# sensors_actuators_shieldv2_1.net
KiCad netlist of a schematic drawn in EAGLE
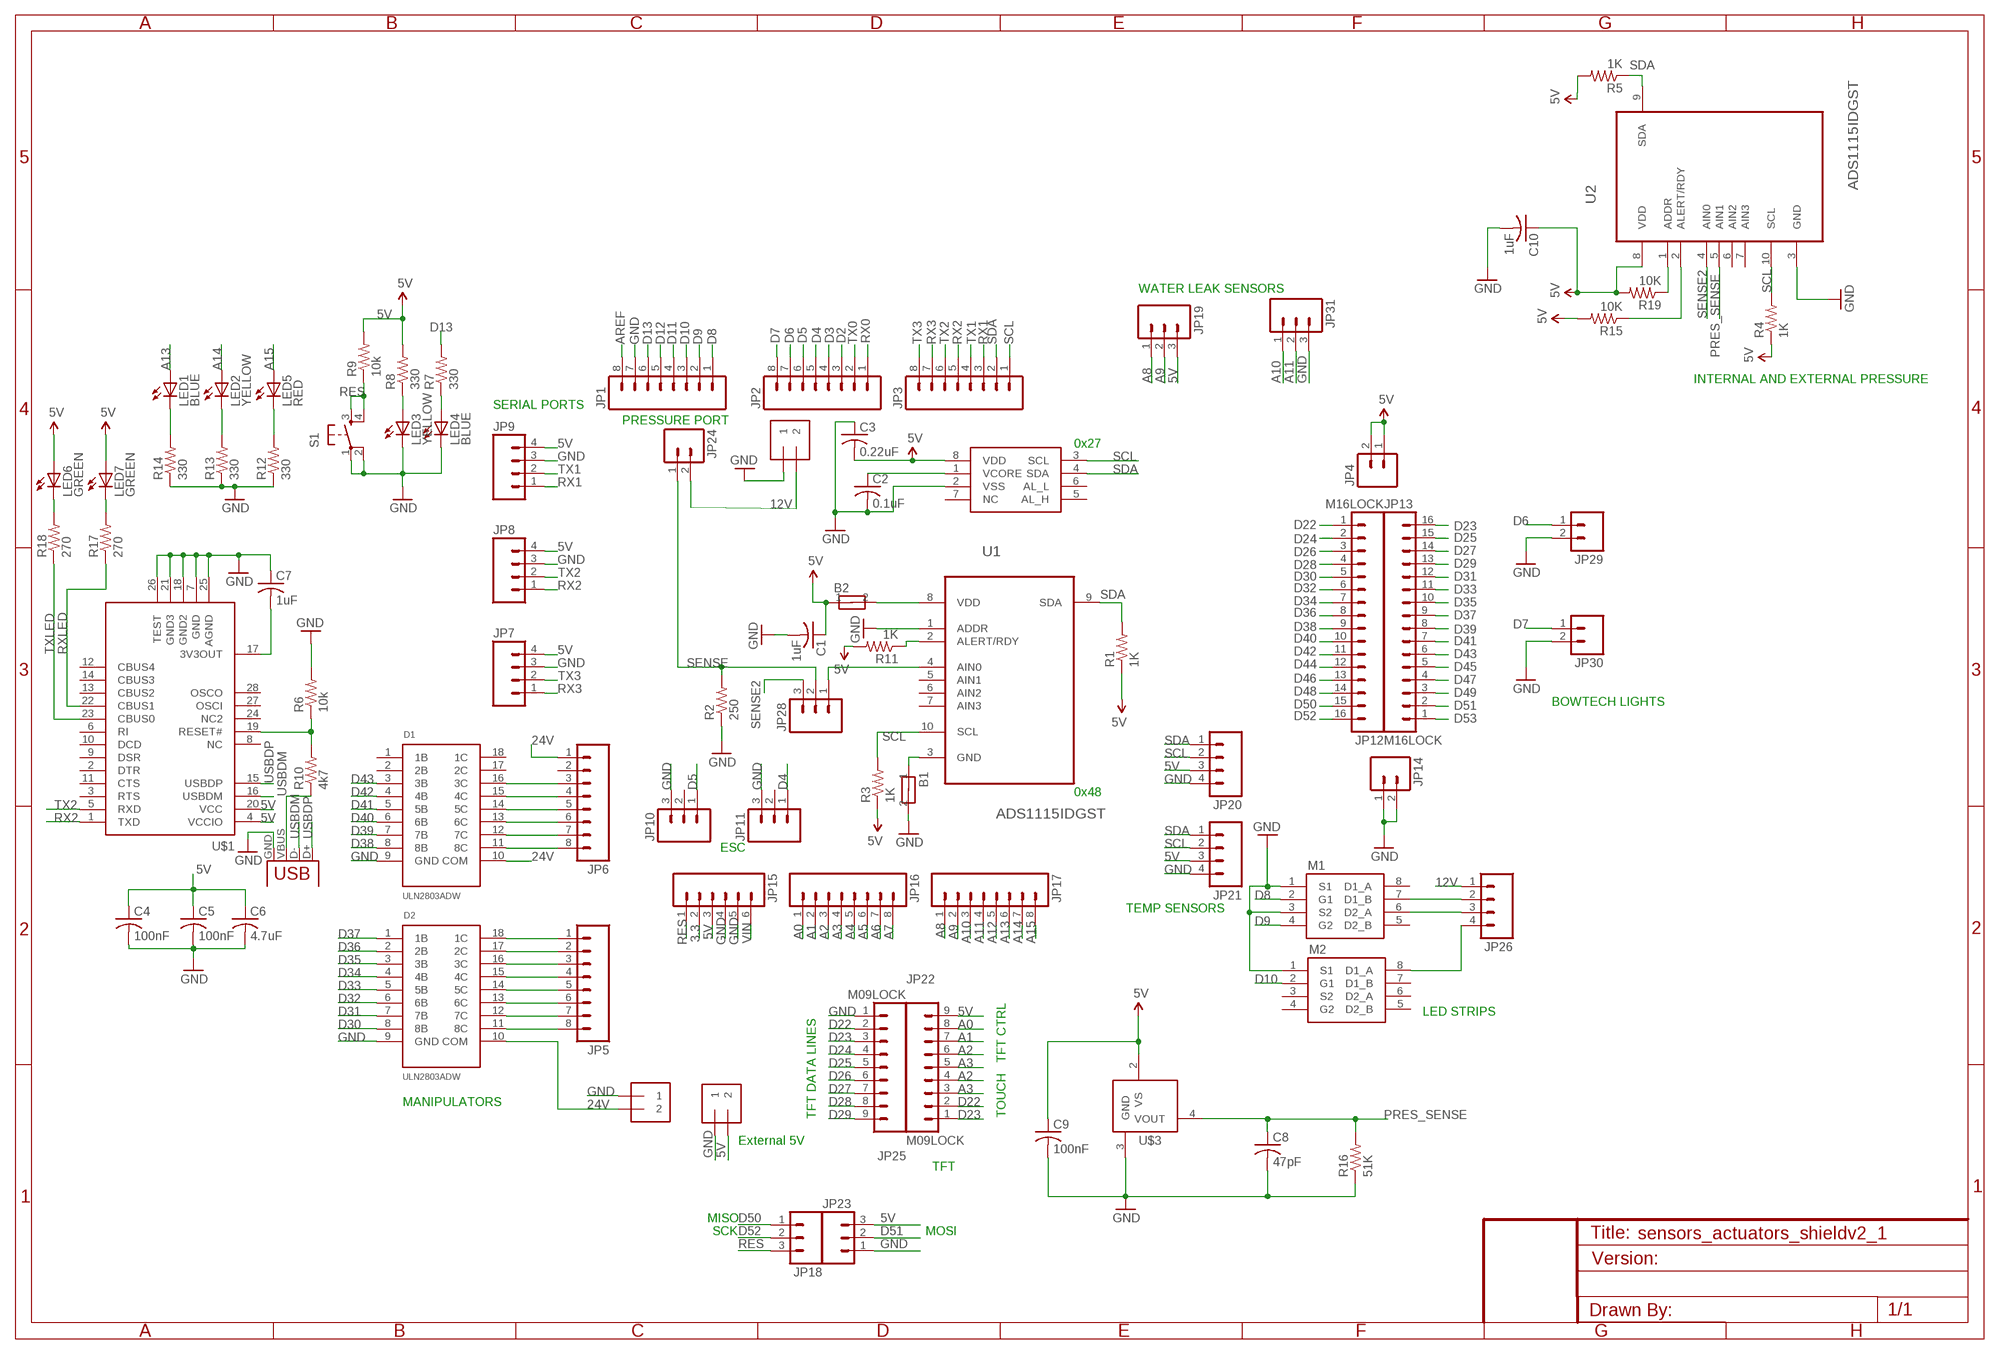
[diagram p0: schematic, sheet 1]

(export (version "E")
  (design (tool "Eeschema 10.0.6"))
  (components
    (comp (ref "B1")
      (value "MMZ2012Y152B0.4OHM,500MA")
      (footprint "eagle-import:0805")
      (fields (field (name "MPN") "MMZ2012Y152B"))
      (libsource (lib "eagle-import") (part "MMZ2012Y152B0.4OHM,500MA"))
    )
    (comp (ref "B2")
      (value "MMZ2012Y152B0.4OHM,500MA")
      (footprint "eagle-import:0805")
      (fields (field (name "MPN") "MMZ2012Y152B"))
      (libsource (lib "eagle-import") (part "MMZ2012Y152B0.4OHM,500MA"))
    )
    (comp (ref "C1")
      (value "1uF")
      (footprint "eagle-import:C0805")
      (fields (field (name "MF") "KEMET") (field (name "MPN") "C0805C105M4RACTU"))
      (libsource (lib "eagle-import") (part "C-USC0805"))
    )
    (comp (ref "C2")
      (value "0.1uF")
      (footprint "eagle-import:C0805")
      (fields (field (name "MPN") "08055C104K4Z2A"))
      (libsource (lib "eagle-import") (part "C-USC0805"))
    )
    (comp (ref "C3")
      (value "0.22uF")
      (footprint "eagle-import:C0805")
      (fields (field (name "MPN") "CGA4J2X8R1E224K125AA"))
      (libsource (lib "eagle-import") (part "C-USC0805"))
    )
    (comp (ref "C4")
      (value "100nF")
      (footprint "eagle-import:C0805")
      (fields (field (name "MPN") "MC0805B104J500CT"))
      (libsource (lib "eagle-import") (part "C-USC0805"))
    )
    (comp (ref "C5")
      (value "100nF")
      (footprint "eagle-import:C0805")
      (fields (field (name "MPN") "MC0805B104J500CT"))
      (libsource (lib "eagle-import") (part "C-USC0805"))
    )
    (comp (ref "C6")
      (value "4.7uF")
      (footprint "eagle-import:C0805")
      (fields (field (name "MPN") "C2012X5R1A475K125AA"))
      (libsource (lib "eagle-import") (part "C-USC0805"))
    )
    (comp (ref "C7")
      (value "1uF")
      (footprint "eagle-import:C0805")
      (fields (field (name "MF") "KEMET") (field (name "MPN") "C0805C105M4RACTU"))
      (libsource (lib "eagle-import") (part "C-USC0805"))
    )
    (comp (ref "C8")
      (value "47pF")
      (footprint "eagle-import:C0805")
      (fields (field (name "MF") "VISHAY/VITRAMON") (field (name "MPN") "VJ0805A470KXAMT"))
      (libsource (lib "eagle-import") (part "C-USC0805"))
    )
    (comp (ref "C9")
      (value "100nF")
      (footprint "eagle-import:C0805")
      (fields (field (name "MPN") "MC0805B104J500CT"))
      (libsource (lib "eagle-import") (part "C-USC0805"))
    )
    (comp (ref "C10")
      (value "1uF")
      (footprint "eagle-import:C0805")
      (fields (field (name "MF") "KEMET") (field (name "MPN") "C0805C105M4RACTU"))
      (libsource (lib "eagle-import") (part "C-USC0805"))
    )
    (comp (ref "D1")
      (value "ULN2803ADW")
      (footprint "eagle-import:SOIC")
      (fields (field (name "MF") "TEXAS INSTRUMENTS"))
      (libsource (lib "eagle-import") (part "ULN2803ADW"))
    )
    (comp (ref "D2")
      (value "ULN2803ADW")
      (footprint "eagle-import:SOIC")
      (fields (field (name "MF") "TEXAS INSTRUMENTS"))
      (libsource (lib "eagle-import") (part "ULN2803ADW"))
    )
    (comp (ref "J1")
      (value "1X2-3.5MM")
      (footprint "eagle-import:1X2-3.5MM")
      (fields (field (name "MPN") "691103110002"))
      (libsource (lib "eagle-import") (part "1X2-3.5MM"))
    )
    (comp (ref "J2")
      (value "1X2-3.5MM")
      (footprint "eagle-import:1X2-3.5MM")
      (fields (field (name "MPN") "691103110002"))
      (libsource (lib "eagle-import") (part "1X2-3.5MM"))
    )
    (comp (ref "J3")
      (value "1X2-3.5MM")
      (footprint "eagle-import:1X2-3.5MM")
      (fields (field (name "MPN") "691103110002"))
      (libsource (lib "eagle-import") (part "1X2-3.5MM"))
    )
    (comp (ref "JP1")
      (value "M08LOCK")
      (footprint "eagle-import:1X08_LOCK")
      (libsource (lib "eagle-import") (part "M08LOCK"))
    )
    (comp (ref "JP2")
      (value "M08LOCK")
      (footprint "eagle-import:1X08_LOCK")
      (libsource (lib "eagle-import") (part "M08LOCK"))
    )
    (comp (ref "JP3")
      (value "M08LOCK")
      (footprint "eagle-import:1X08_LOCK")
      (libsource (lib "eagle-import") (part "M08LOCK"))
    )
    (comp (ref "JP4")
      (value "M02LOCK")
      (footprint "eagle-import:1X02_LOCK")
      (libsource (lib "eagle-import") (part "M02LOCK"))
    )
    (comp (ref "JP5")
      (value "M08LOCK")
      (footprint "eagle-import:1X08_LOCK")
      (libsource (lib "eagle-import") (part "M08LOCK"))
    )
    (comp (ref "JP6")
      (value "M08LOCK")
      (footprint "eagle-import:1X08_LOCK")
      (libsource (lib "eagle-import") (part "M08LOCK"))
    )
    (comp (ref "JP7")
      (value "M04LOCK")
      (footprint "eagle-import:1X04_LOCK")
      (libsource (lib "eagle-import") (part "M04LOCK"))
    )
    (comp (ref "JP8")
      (value "M04LOCK")
      (footprint "eagle-import:1X04_LOCK")
      (libsource (lib "eagle-import") (part "M04LOCK"))
    )
    (comp (ref "JP9")
      (value "M04LOCK")
      (footprint "eagle-import:1X04_LOCK")
      (libsource (lib "eagle-import") (part "M04LOCK"))
    )
    (comp (ref "JP10")
      (value "M03LOCK")
      (footprint "eagle-import:1X03_LOCK")
      (libsource (lib "eagle-import") (part "M03LOCK"))
    )
    (comp (ref "JP11")
      (value "M03LOCK")
      (footprint "eagle-import:1X03_LOCK")
      (libsource (lib "eagle-import") (part "M03LOCK"))
    )
    (comp (ref "JP12")
      (value "M16LOCK")
      (footprint "eagle-import:1X16_LOCK")
      (libsource (lib "eagle-import") (part "M16LOCK"))
    )
    (comp (ref "JP13")
      (value "M16LOCK")
      (footprint "eagle-import:1X16_LOCK")
      (libsource (lib "eagle-import") (part "M16LOCK"))
    )
    (comp (ref "JP14")
      (value "M02LOCK")
      (footprint "eagle-import:1X02_LOCK")
      (libsource (lib "eagle-import") (part "M02LOCK"))
    )
    (comp (ref "JP15")
      (value "M06LOCK")
      (footprint "eagle-import:1X06_LOCK")
      (libsource (lib "eagle-import") (part "M06LOCK"))
    )
    (comp (ref "JP16")
      (value "M08LOCK")
      (footprint "eagle-import:1X08_LOCK")
      (libsource (lib "eagle-import") (part "M08LOCK"))
    )
    (comp (ref "JP17")
      (value "M08LOCK")
      (footprint "eagle-import:1X08_LOCK")
      (libsource (lib "eagle-import") (part "M08LOCK"))
    )
    (comp (ref "JP18")
      (value "M03LOCK")
      (footprint "eagle-import:1X03_LOCK")
      (libsource (lib "eagle-import") (part "M03LOCK"))
    )
    (comp (ref "JP19")
      (value "M03LOCK")
      (footprint "eagle-import:1X03_LOCK")
      (libsource (lib "eagle-import") (part "M03LOCK"))
    )
    (comp (ref "JP20")
      (value "M04LOCK")
      (footprint "eagle-import:1X04_LOCK")
      (libsource (lib "eagle-import") (part "M04LOCK"))
    )
    (comp (ref "JP21")
      (value "M04LOCK")
      (footprint "eagle-import:1X04_LOCK")
      (libsource (lib "eagle-import") (part "M04LOCK"))
    )
    (comp (ref "JP22")
      (value "M09LOCK")
      (footprint "eagle-import:1X09_LOCK")
      (libsource (lib "eagle-import") (part "M09LOCK"))
    )
    (comp (ref "JP23")
      (value "M03LOCK")
      (footprint "eagle-import:1X03_LOCK")
      (libsource (lib "eagle-import") (part "M03LOCK"))
    )
    (comp (ref "JP24")
      (value "M02LOCK")
      (footprint "eagle-import:1X02_LOCK")
      (libsource (lib "eagle-import") (part "M02LOCK"))
    )
    (comp (ref "JP25")
      (value "M09LOCK")
      (footprint "eagle-import:1X09_LOCK")
      (libsource (lib "eagle-import") (part "M09LOCK"))
    )
    (comp (ref "JP26")
      (value "M04LOCK")
      (footprint "eagle-import:1X04_LOCK")
      (libsource (lib "eagle-import") (part "M04LOCK"))
    )
    (comp (ref "JP27")
      (value "USBSMD")
      (footprint "eagle-import:USB-MINIB")
      (fields (field (name "MF") "MOLEX") (field (name "MPN") "67503-1020"))
      (libsource (lib "eagle-import") (part "USBSMD"))
    )
    (comp (ref "JP28")
      (value "M03LOCK")
      (footprint "eagle-import:1X03_LOCK")
      (libsource (lib "eagle-import") (part "M03LOCK"))
    )
    (comp (ref "JP29")
      (value "M02LOCK")
      (footprint "eagle-import:1X02_LOCK")
      (libsource (lib "eagle-import") (part "M02LOCK"))
    )
    (comp (ref "JP30")
      (value "M02LOCK")
      (footprint "eagle-import:1X02_LOCK")
      (libsource (lib "eagle-import") (part "M02LOCK"))
    )
    (comp (ref "JP31")
      (value "M03LOCK")
      (footprint "eagle-import:1X03_LOCK")
      (libsource (lib "eagle-import") (part "M03LOCK"))
    )
    (comp (ref "LED1")
      (value "BLUE")
      (footprint "eagle-import:CHIPLED_0805")
      (fields (field (name "MPN") "150080BS75000"))
      (libsource (lib "eagle-import") (part "LEDCHIPLED_0805"))
    )
    (comp (ref "LED2")
      (value "YELLOW")
      (footprint "eagle-import:CHIPLED_0805")
      (fields (field (name "MPN") "KP-2012SYCK-J3"))
      (libsource (lib "eagle-import") (part "LEDCHIPLED_0805"))
    )
    (comp (ref "LED3")
      (value "YELLOW")
      (footprint "eagle-import:CHIPLED_0805")
      (fields (field (name "MPN") "KP-2012SYCK-J3"))
      (libsource (lib "eagle-import") (part "LEDCHIPLED_0805"))
    )
    (comp (ref "LED4")
      (value "BLUE")
      (footprint "eagle-import:CHIPLED_0805")
      (fields (field (name "MPN") "150080BS75000"))
      (libsource (lib "eagle-import") (part "LEDCHIPLED_0805"))
    )
    (comp (ref "LED5")
      (value "RED")
      (footprint "eagle-import:CHIPLED_0805")
      (fields (field (name "MPN") "OVS-0808"))
      (libsource (lib "eagle-import") (part "LEDCHIPLED_0805"))
    )
    (comp (ref "LED6")
      (value "GREEN")
      (footprint "eagle-import:CHIPLED_0805")
      (fields (field (name "MF") "SLI (CML/IDI)") (field (name "MPN") "CMD17-21VGC/TR8"))
      (libsource (lib "eagle-import") (part "LEDCHIPLED_0805"))
    )
    (comp (ref "LED7")
      (value "GREEN")
      (footprint "eagle-import:CHIPLED_0805")
      (fields (field (name "MF") "SLI (CML/IDI)") (field (name "MPN") "CMD17-21VGC/TR8"))
      (libsource (lib "eagle-import") (part "LEDCHIPLED_0805"))
    )
    (comp (ref "M1")
      (value "IRF7910PBF")
      (footprint "eagle-import:SO-8")
      (libsource (lib "eagle-import") (part "IRF7910PBF"))
    )
    (comp (ref "M2")
      (value "IRF7910PBF")
      (footprint "eagle-import:SO-8")
      (libsource (lib "eagle-import") (part "IRF7910PBF"))
    )
    (comp (ref "R1")
      (value "1K")
      (footprint "eagle-import:M0805")
      (fields (field (name "MF") "VISHAY/DALE") (field (name "MPN") "CRCW08051K00FKTA"))
      (libsource (lib "eagle-import") (part "R-US_M0805"))
    )
    (comp (ref "R2")
      (value "250")
      (footprint "eagle-import:M0805")
      (fields (field (name "MPN") "PLTT0805Z2500AGTS"))
      (libsource (lib "eagle-import") (part "R-US_M0805"))
    )
    (comp (ref "R3")
      (value "1K")
      (footprint "eagle-import:M0805")
      (fields (field (name "MF") "VISHAY/DALE") (field (name "MPN") "CRCW08051K00FKTA"))
      (libsource (lib "eagle-import") (part "R-US_M0805"))
    )
    (comp (ref "R4")
      (value "1K")
      (footprint "eagle-import:M0805")
      (fields (field (name "MF") "VISHAY/DALE") (field (name "MPN") "CRCW08051K00FKTA"))
      (libsource (lib "eagle-import") (part "R-US_M0805"))
    )
    (comp (ref "R5")
      (value "1K")
      (footprint "eagle-import:M0805")
      (fields (field (name "MF") "VISHAY/DALE") (field (name "MPN") "CRCW08051K00FKTA"))
      (libsource (lib "eagle-import") (part "R-US_M0805"))
    )
    (comp (ref "R6")
      (value "10k")
      (footprint "eagle-import:M0805")
      (fields (field (name "MPN") "MCHP05W4F1002T5E"))
      (libsource (lib "eagle-import") (part "R-US_M0805"))
    )
    (comp (ref "R7")
      (value "330")
      (footprint "eagle-import:M0805")
      (fields (field (name "MPN") "MCHP05W4F3300T5E"))
      (libsource (lib "eagle-import") (part "R-US_M0805"))
    )
    (comp (ref "R8")
      (value "330")
      (footprint "eagle-import:M0805")
      (fields (field (name "MPN") "MCHP05W4F3300T5E"))
      (libsource (lib "eagle-import") (part "R-US_M0805"))
    )
    (comp (ref "R9")
      (value "10k")
      (footprint "eagle-import:M0805")
      (fields (field (name "MPN") "MCHP05W4F1002T5E"))
      (libsource (lib "eagle-import") (part "R-US_M0805"))
    )
    (comp (ref "R10")
      (value "4k7")
      (footprint "eagle-import:M0805")
      (fields (field (name "MPN") "CR0805-JW-472ELF"))
      (libsource (lib "eagle-import") (part "R-US_M0805"))
    )
    (comp (ref "R11")
      (value "1K")
      (footprint "eagle-import:M0805")
      (fields (field (name "MF") "VISHAY/DALE") (field (name "MPN") "CRCW08051K00FKTA"))
      (libsource (lib "eagle-import") (part "R-US_M0805"))
    )
    (comp (ref "R12")
      (value "330")
      (footprint "eagle-import:M0805")
      (fields (field (name "MPN") "MCHP05W4F3300T5E"))
      (libsource (lib "eagle-import") (part "R-US_M0805"))
    )
    (comp (ref "R13")
      (value "330")
      (footprint "eagle-import:M0805")
      (fields (field (name "MPN") "MCHP05W4F3300T5E"))
      (libsource (lib "eagle-import") (part "R-US_M0805"))
    )
    (comp (ref "R14")
      (value "330")
      (footprint "eagle-import:M0805")
      (fields (field (name "MPN") "MCHP05W4F3300T5E"))
      (libsource (lib "eagle-import") (part "R-US_M0805"))
    )
    (comp (ref "R15")
      (value "10K")
      (footprint "eagle-import:M0805")
      (libsource (lib "eagle-import") (part "R-US_M0805"))
    )
    (comp (ref "R16")
      (value "51K")
      (footprint "eagle-import:M0805")
      (fields (field (name "MF") "OUTSOURCE ITEM") (field (name "MPN") "RR1220P-513-B-T5"))
      (libsource (lib "eagle-import") (part "R-US_M0805"))
    )
    (comp (ref "R17")
      (value "270")
      (footprint "eagle-import:M0805")
      (fields (field (name "MPN") "MC0805S8F2700T5E"))
      (libsource (lib "eagle-import") (part "R-US_M0805"))
    )
    (comp (ref "R18")
      (value "270")
      (footprint "eagle-import:M0805")
      (fields (field (name "MPN") "MC0805S8F2700T5E"))
      (libsource (lib "eagle-import") (part "R-US_M0805"))
    )
    (comp (ref "R19")
      (value "10K")
      (footprint "eagle-import:M0805")
      (libsource (lib "eagle-import") (part "R-US_M0805"))
    )
    (comp (ref "S1")
      (value "TAC_SWITCHPTH")
      (footprint "eagle-import:TACTILE-PTH")
      (libsource (lib "eagle-import") (part "TAC_SWITCHPTH"))
    )
    (comp (ref "U$1")
      (value "FT232RL")
      (footprint "eagle-import:SSOP-28")
      (libsource (lib "eagle-import") (part "FT232RL"))
    )
    (comp (ref "U$2")
      (value "HIH6130")
      (footprint "eagle-import:SO-8")
      (fields (field (name "MPN") "HIH6131-021-001"))
      (libsource (lib "eagle-import") (part "HIH6130"))
    )
    (comp (ref "U$3")
      (value "MPXH6250A")
      (footprint "eagle-import:SSOP-8")
      (libsource (lib "eagle-import") (part "MPXH6250A"))
    )
    (comp (ref "U1")
      (value "ADS1115IDGST")
      (footprint "eagle-import:SOP50P490X110-10N")
      (libsource (lib "eagle-import") (part "ADS1115IDGST"))
    )
    (comp (ref "U2")
      (value "ADS1115IDGST")
      (footprint "eagle-import:SOP50P490X110-10N")
      (libsource (lib "eagle-import") (part "ADS1115IDGST"))
    )
  )
  (nets
    (net (code "1") (name "/3.3") (class "Default")
      (node (ref "JP15") (pin "2") (pinfunction "2_2") (pintype "passive"))
    )
    (net (code "2") (name "/12V") (class "Default")
      (node (ref "J1") (pin "2") (pinfunction "2_2") (pintype "passive"))
      (node (ref "JP24") (pin "2") (pinfunction "2_2") (pintype "passive"))
      (node (ref "JP26") (pin "1") (pinfunction "1_1") (pintype "passive"))
    )
    (net (code "3") (name "/24V") (class "Default")
      (node (ref "D1") (pin "10") (pinfunction "COM_10") (pintype "bidirectional"))
      (node (ref "D2") (pin "10") (pinfunction "COM_10") (pintype "bidirectional"))
      (node (ref "J2") (pin "2") (pinfunction "2_2") (pintype "passive"))
      (node (ref "JP6") (pin "1") (pinfunction "1_1") (pintype "passive"))
    )
    (net (code "4") (name "/A0") (class "Default")
      (node (ref "JP16") (pin "1") (pinfunction "1_1") (pintype "passive"))
      (node (ref "JP22") (pin "8") (pinfunction "8_8") (pintype "passive"))
    )
    (net (code "5") (name "/A1") (class "Default")
      (node (ref "JP16") (pin "2") (pinfunction "2_2") (pintype "passive"))
      (node (ref "JP22") (pin "7") (pinfunction "7_7") (pintype "passive"))
    )
    (net (code "6") (name "/A2") (class "Default")
      (node (ref "JP16") (pin "3") (pinfunction "3_3") (pintype "passive"))
      (node (ref "JP22") (pin "4") (pinfunction "4_4") (pintype "passive"))
      (node (ref "JP22") (pin "6") (pinfunction "6_6") (pintype "passive"))
    )
    (net (code "7") (name "/A3") (class "Default")
      (node (ref "JP16") (pin "4") (pinfunction "4_4") (pintype "passive"))
      (node (ref "JP22") (pin "3") (pinfunction "3_3") (pintype "passive"))
      (node (ref "JP22") (pin "5") (pinfunction "5_5") (pintype "passive"))
    )
    (net (code "8") (name "/A4") (class "Default")
      (node (ref "JP16") (pin "5") (pinfunction "5_5") (pintype "passive"))
    )
    (net (code "9") (name "/A5") (class "Default")
      (node (ref "JP16") (pin "6") (pinfunction "6_6") (pintype "passive"))
    )
    (net (code "10") (name "/A6") (class "Default")
      (node (ref "JP16") (pin "7") (pinfunction "7_7") (pintype "passive"))
    )
    (net (code "11") (name "/A7") (class "Default")
      (node (ref "JP16") (pin "8") (pinfunction "8_8") (pintype "passive"))
    )
    (net (code "12") (name "/A8") (class "Default")
      (node (ref "JP17") (pin "1") (pinfunction "1_1") (pintype "passive"))
      (node (ref "JP19") (pin "1") (pinfunction "1_1") (pintype "passive"))
    )
    (net (code "13") (name "/A9") (class "Default")
      (node (ref "JP17") (pin "2") (pinfunction "2_2") (pintype "passive"))
      (node (ref "JP19") (pin "2") (pinfunction "2_2") (pintype "passive"))
    )
    (net (code "14") (name "/A10") (class "Default")
      (node (ref "JP17") (pin "3") (pinfunction "3_3") (pintype "passive"))
      (node (ref "JP31") (pin "1") (pinfunction "1_1") (pintype "passive"))
    )
    (net (code "15") (name "/A11") (class "Default")
      (node (ref "JP17") (pin "4") (pinfunction "4_4") (pintype "passive"))
      (node (ref "JP31") (pin "2") (pinfunction "2_2") (pintype "passive"))
    )
    (net (code "16") (name "/A12") (class "Default")
      (node (ref "JP17") (pin "5") (pinfunction "5_5") (pintype "passive"))
    )
    (net (code "17") (name "/A13") (class "Default")
      (node (ref "JP17") (pin "6") (pinfunction "6_6") (pintype "passive"))
      (node (ref "LED1") (pin "A") (pinfunction "A_A") (pintype "passive"))
    )
    (net (code "18") (name "/A14") (class "Default")
      (node (ref "JP17") (pin "7") (pinfunction "7_7") (pintype "passive"))
      (node (ref "LED2") (pin "A") (pinfunction "A_A") (pintype "passive"))
    )
    (net (code "19") (name "/A15") (class "Default")
      (node (ref "JP17") (pin "8") (pinfunction "8_8") (pintype "passive"))
      (node (ref "LED5") (pin "A") (pinfunction "A_A") (pintype "passive"))
    )
    (net (code "20") (name "/AREF") (class "Default")
      (node (ref "JP1") (pin "8") (pinfunction "8_8") (pintype "passive"))
    )
    (net (code "21") (name "/D2") (class "Default")
      (node (ref "JP2") (pin "3") (pinfunction "3_3") (pintype "passive"))
    )
    (net (code "22") (name "/D3") (class "Default")
      (node (ref "JP2") (pin "4") (pinfunction "4_4") (pintype "passive"))
    )
    (net (code "23") (name "/D4") (class "Default")
      (node (ref "JP11") (pin "1") (pinfunction "1_1") (pintype "passive"))
      (node (ref "JP2") (pin "5") (pinfunction "5_5") (pintype "passive"))
    )
    (net (code "24") (name "/D5") (class "Default")
      (node (ref "JP10") (pin "1") (pinfunction "1_1") (pintype "passive"))
      (node (ref "JP2") (pin "6") (pinfunction "6_6") (pintype "passive"))
    )
    (net (code "25") (name "/D6") (class "Default")
      (node (ref "JP2") (pin "7") (pinfunction "7_7") (pintype "passive"))
      (node (ref "JP29") (pin "1") (pinfunction "1_1") (pintype "passive"))
    )
    (net (code "26") (name "/D7") (class "Default")
      (node (ref "JP2") (pin "8") (pinfunction "8_8") (pintype "passive"))
      (node (ref "JP30") (pin "1") (pinfunction "1_1") (pintype "passive"))
    )
    (net (code "27") (name "/D8") (class "Default")
      (node (ref "JP1") (pin "1") (pinfunction "1_1") (pintype "passive"))
      (node (ref "M1") (pin "2") (pinfunction "G1_2") (pintype "bidirectional"))
    )
    (net (code "28") (name "/D9") (class "Default")
      (node (ref "JP1") (pin "2") (pinfunction "2_2") (pintype "passive"))
      (node (ref "M1") (pin "4") (pinfunction "G2_4") (pintype "bidirectional"))
    )
    (net (code "29") (name "/D10") (class "Default")
      (node (ref "JP1") (pin "3") (pinfunction "3_3") (pintype "passive"))
      (node (ref "M2") (pin "2") (pinfunction "G1_2") (pintype "bidirectional"))
    )
    (net (code "30") (name "/D11") (class "Default")
      (node (ref "JP1") (pin "4") (pinfunction "4_4") (pintype "passive"))
    )
    (net (code "31") (name "/D12") (class "Default")
      (node (ref "JP1") (pin "5") (pinfunction "5_5") (pintype "passive"))
    )
    (net (code "32") (name "/D13") (class "Default")
      (node (ref "JP1") (pin "6") (pinfunction "6_6") (pintype "passive"))
      (node (ref "R7") (pin "2") (pinfunction "2_2") (pintype "passive"))
    )
    (net (code "33") (name "/D22") (class "Default")
      (node (ref "JP12") (pin "1") (pinfunction "1_1") (pintype "passive"))
      (node (ref "JP22") (pin "2") (pinfunction "2_2") (pintype "passive"))
      (node (ref "JP25") (pin "2") (pinfunction "2_2") (pintype "passive"))
    )
    (net (code "34") (name "/D23") (class "Default")
      (node (ref "JP13") (pin "16") (pinfunction "16_16") (pintype "passive"))
      (node (ref "JP22") (pin "1") (pinfunction "1_1") (pintype "passive"))
      (node (ref "JP25") (pin "3") (pinfunction "3_3") (pintype "passive"))
    )
    (net (code "35") (name "/D24") (class "Default")
      (node (ref "JP12") (pin "2") (pinfunction "2_2") (pintype "passive"))
      (node (ref "JP25") (pin "4") (pinfunction "4_4") (pintype "passive"))
    )
    (net (code "36") (name "/D25") (class "Default")
      (node (ref "JP13") (pin "15") (pinfunction "15_15") (pintype "passive"))
      (node (ref "JP25") (pin "5") (pinfunction "5_5") (pintype "passive"))
    )
    (net (code "37") (name "/D26") (class "Default")
      (node (ref "JP12") (pin "3") (pinfunction "3_3") (pintype "passive"))
      (node (ref "JP25") (pin "6") (pinfunction "6_6") (pintype "passive"))
    )
    (net (code "38") (name "/D27") (class "Default")
      (node (ref "JP13") (pin "14") (pinfunction "14_14") (pintype "passive"))
      (node (ref "JP25") (pin "7") (pinfunction "7_7") (pintype "passive"))
    )
    (net (code "39") (name "/D28") (class "Default")
      (node (ref "JP12") (pin "4") (pinfunction "4_4") (pintype "passive"))
      (node (ref "JP25") (pin "8") (pinfunction "8_8") (pintype "passive"))
    )
    (net (code "40") (name "/D29") (class "Default")
      (node (ref "JP13") (pin "13") (pinfunction "13_13") (pintype "passive"))
      (node (ref "JP25") (pin "9") (pinfunction "9_9") (pintype "passive"))
    )
    (net (code "41") (name "/D30") (class "Default")
      (node (ref "D2") (pin "8") (pinfunction "8B_8") (pintype "bidirectional"))
      (node (ref "JP12") (pin "5") (pinfunction "5_5") (pintype "passive"))
    )
    (net (code "42") (name "/D31") (class "Default")
      (node (ref "D2") (pin "7") (pinfunction "7B_7") (pintype "bidirectional"))
      (node (ref "JP13") (pin "12") (pinfunction "12_12") (pintype "passive"))
    )
    (net (code "43") (name "/D32") (class "Default")
      (node (ref "D2") (pin "6") (pinfunction "6B_6") (pintype "bidirectional"))
      (node (ref "JP12") (pin "6") (pinfunction "6_6") (pintype "passive"))
    )
    (net (code "44") (name "/D33") (class "Default")
      (node (ref "D2") (pin "5") (pinfunction "5B_5") (pintype "bidirectional"))
      (node (ref "JP13") (pin "11") (pinfunction "11_11") (pintype "passive"))
    )
    (net (code "45") (name "/D34") (class "Default")
      (node (ref "D2") (pin "4") (pinfunction "4B_4") (pintype "bidirectional"))
      (node (ref "JP12") (pin "7") (pinfunction "7_7") (pintype "passive"))
    )
    (net (code "46") (name "/D35") (class "Default")
      (node (ref "D2") (pin "3") (pinfunction "3B_3") (pintype "bidirectional"))
      (node (ref "JP13") (pin "10") (pinfunction "10_10") (pintype "passive"))
    )
    (net (code "47") (name "/D36") (class "Default")
      (node (ref "D2") (pin "2") (pinfunction "2B_2") (pintype "bidirectional"))
      (node (ref "JP12") (pin "8") (pinfunction "8_8") (pintype "passive"))
    )
    (net (code "48") (name "/D37") (class "Default")
      (node (ref "D2") (pin "1") (pinfunction "1B_1") (pintype "bidirectional"))
      (node (ref "JP13") (pin "9") (pinfunction "9_9") (pintype "passive"))
    )
    (net (code "49") (name "/D38") (class "Default")
      (node (ref "D1") (pin "8") (pinfunction "8B_8") (pintype "bidirectional"))
      (node (ref "JP12") (pin "9") (pinfunction "9_9") (pintype "passive"))
    )
    (net (code "50") (name "/D39") (class "Default")
      (node (ref "D1") (pin "7") (pinfunction "7B_7") (pintype "bidirectional"))
      (node (ref "JP13") (pin "8") (pinfunction "8_8") (pintype "passive"))
    )
    (net (code "51") (name "/D40") (class "Default")
      (node (ref "D1") (pin "6") (pinfunction "6B_6") (pintype "bidirectional"))
      (node (ref "JP12") (pin "10") (pinfunction "10_10") (pintype "passive"))
    )
    (net (code "52") (name "/D41") (class "Default")
      (node (ref "D1") (pin "5") (pinfunction "5B_5") (pintype "bidirectional"))
      (node (ref "JP13") (pin "7") (pinfunction "7_7") (pintype "passive"))
    )
    (net (code "53") (name "/D42") (class "Default")
      (node (ref "D1") (pin "4") (pinfunction "4B_4") (pintype "bidirectional"))
      (node (ref "JP12") (pin "11") (pinfunction "11_11") (pintype "passive"))
    )
    (net (code "54") (name "/D43") (class "Default")
      (node (ref "D1") (pin "3") (pinfunction "3B_3") (pintype "bidirectional"))
      (node (ref "JP13") (pin "6") (pinfunction "6_6") (pintype "passive"))
    )
    (net (code "55") (name "/D44") (class "Default")
      (node (ref "JP12") (pin "12") (pinfunction "12_12") (pintype "passive"))
    )
    (net (code "56") (name "/D45") (class "Default")
      (node (ref "JP13") (pin "5") (pinfunction "5_5") (pintype "passive"))
    )
    (net (code "57") (name "/D46") (class "Default")
      (node (ref "JP12") (pin "13") (pinfunction "13_13") (pintype "passive"))
    )
    (net (code "58") (name "/D47") (class "Default")
      (node (ref "JP13") (pin "4") (pinfunction "4_4") (pintype "passive"))
    )
    (net (code "59") (name "/D48") (class "Default")
      (node (ref "JP12") (pin "14") (pinfunction "14_14") (pintype "passive"))
    )
    (net (code "60") (name "/D49") (class "Default")
      (node (ref "JP13") (pin "3") (pinfunction "3_3") (pintype "passive"))
    )
    (net (code "61") (name "/D50") (class "Default")
      (node (ref "JP12") (pin "15") (pinfunction "15_15") (pintype "passive"))
      (node (ref "JP18") (pin "1") (pinfunction "1_1") (pintype "passive"))
    )
    (net (code "62") (name "/D51") (class "Default")
      (node (ref "JP13") (pin "2") (pinfunction "2_2") (pintype "passive"))
      (node (ref "JP23") (pin "2") (pinfunction "2_2") (pintype "passive"))
    )
    (net (code "63") (name "/D52") (class "Default")
      (node (ref "JP12") (pin "16") (pinfunction "16_16") (pintype "passive"))
      (node (ref "JP18") (pin "2") (pinfunction "2_2") (pintype "passive"))
    )
    (net (code "64") (name "/D53") (class "Default")
      (node (ref "JP13") (pin "1") (pinfunction "1_1") (pintype "passive"))
    )
    (net (code "65") (name "/PRES_SENSE") (class "Default")
      (node (ref "C8") (pin "1") (pinfunction "1_1") (pintype "passive"))
      (node (ref "R16") (pin "2") (pinfunction "2_2") (pintype "passive"))
      (node (ref "U$3") (pin "4") (pinfunction "VOUT_4") (pintype "bidirectional"))
      (node (ref "U2") (pin "5") (pinfunction "AIN1_5") (pintype "input"))
    )
    (net (code "66") (name "/RES") (class "Default")
      (node (ref "JP15") (pin "1") (pinfunction "1_1") (pintype "passive"))
      (node (ref "JP18") (pin "3") (pinfunction "3_3") (pintype "passive"))
      (node (ref "R9") (pin "1") (pinfunction "1_1") (pintype "passive"))
      (node (ref "S1") (pin "3") (pinfunction "3_3") (pintype "passive"))
      (node (ref "S1") (pin "4") (pinfunction "4_4") (pintype "passive"))
    )
    (net (code "67") (name "/RX0") (class "Default")
      (node (ref "JP2") (pin "1") (pinfunction "1_1") (pintype "passive"))
    )
    (net (code "68") (name "/RX1") (class "Default")
      (node (ref "JP3") (pin "3") (pinfunction "3_3") (pintype "passive"))
      (node (ref "JP9") (pin "1") (pinfunction "1_1") (pintype "passive"))
    )
    (net (code "69") (name "/RX2") (class "Default")
      (node (ref "JP3") (pin "5") (pinfunction "5_5") (pintype "passive"))
      (node (ref "JP8") (pin "1") (pinfunction "1_1") (pintype "passive"))
      (node (ref "U$1") (pin "1") (pinfunction "TXD_1") (pintype "bidirectional"))
    )
    (net (code "70") (name "/RX3") (class "Default")
      (node (ref "JP3") (pin "7") (pinfunction "7_7") (pintype "passive"))
      (node (ref "JP7") (pin "1") (pinfunction "1_1") (pintype "passive"))
    )
    (net (code "71") (name "/RXLED") (class "Default")
      (node (ref "R17") (pin "1") (pinfunction "1_1") (pintype "passive"))
      (node (ref "U$1") (pin "22") (pinfunction "CBUS1_22") (pintype "bidirectional"))
    )
    (net (code "72") (name "/SCL") (class "Default")
      (node (ref "JP20") (pin "2") (pinfunction "2_2") (pintype "passive"))
      (node (ref "JP21") (pin "2") (pinfunction "2_2") (pintype "passive"))
      (node (ref "JP3") (pin "1") (pinfunction "1_1") (pintype "passive"))
      (node (ref "R3") (pin "2") (pinfunction "2_2") (pintype "passive"))
      (node (ref "R4") (pin "2") (pinfunction "2_2") (pintype "passive"))
      (node (ref "U$2") (pin "3") (pinfunction "SCL_3") (pintype "bidirectional"))
      (node (ref "U1") (pin "10") (pinfunction "SCL_10") (pintype "input"))
      (node (ref "U2") (pin "10") (pinfunction "SCL_10") (pintype "input"))
    )
    (net (code "73") (name "/SDA") (class "Default")
      (node (ref "JP20") (pin "1") (pinfunction "1_1") (pintype "passive"))
      (node (ref "JP21") (pin "1") (pinfunction "1_1") (pintype "passive"))
      (node (ref "JP3") (pin "2") (pinfunction "2_2") (pintype "passive"))
      (node (ref "R1") (pin "2") (pinfunction "2_2") (pintype "passive"))
      (node (ref "R5") (pin "1") (pinfunction "1_1") (pintype "passive"))
      (node (ref "U$2") (pin "4") (pinfunction "SDA_4") (pintype "bidirectional"))
      (node (ref "U1") (pin "9") (pinfunction "SDA_9") (pintype "bidirectional"))
      (node (ref "U2") (pin "9") (pinfunction "SDA_9") (pintype "bidirectional"))
    )
    (net (code "74") (name "/SENSE") (class "Default")
      (node (ref "JP24") (pin "1") (pinfunction "1_1") (pintype "passive"))
      (node (ref "JP28") (pin "2") (pinfunction "2_2") (pintype "passive"))
      (node (ref "R2") (pin "2") (pinfunction "2_2") (pintype "passive"))
    )
    (net (code "75") (name "/SENSE2") (class "Default")
      (node (ref "JP28") (pin "3") (pinfunction "3_3") (pintype "passive"))
      (node (ref "U2") (pin "4") (pinfunction "AIN0_4") (pintype "input"))
    )
    (net (code "76") (name "/TX0") (class "Default")
      (node (ref "JP2") (pin "2") (pinfunction "2_2") (pintype "passive"))
    )
    (net (code "77") (name "/TX1") (class "Default")
      (node (ref "JP3") (pin "4") (pinfunction "4_4") (pintype "passive"))
      (node (ref "JP9") (pin "2") (pinfunction "2_2") (pintype "passive"))
    )
    (net (code "78") (name "/TX2") (class "Default")
      (node (ref "JP3") (pin "6") (pinfunction "6_6") (pintype "passive"))
      (node (ref "JP8") (pin "2") (pinfunction "2_2") (pintype "passive"))
      (node (ref "U$1") (pin "5") (pinfunction "RXD_5") (pintype "bidirectional"))
    )
    (net (code "79") (name "/TX3") (class "Default")
      (node (ref "JP3") (pin "8") (pinfunction "8_8") (pintype "passive"))
      (node (ref "JP7") (pin "2") (pinfunction "2_2") (pintype "passive"))
    )
    (net (code "80") (name "/TXLED") (class "Default")
      (node (ref "R18") (pin "1") (pinfunction "1_1") (pintype "passive"))
      (node (ref "U$1") (pin "23") (pinfunction "CBUS0_23") (pintype "bidirectional"))
    )
    (net (code "81") (name "/USBDM") (class "Default")
      (node (ref "JP27") (pin "D-") (pinfunction "D-_D-") (pintype "bidirectional"))
      (node (ref "U$1") (pin "16") (pinfunction "USBDM_16") (pintype "bidirectional"))
    )
    (net (code "82") (name "/USBDP") (class "Default")
      (node (ref "JP27") (pin "D+") (pinfunction "D+_D+") (pintype "bidirectional"))
      (node (ref "U$1") (pin "15") (pinfunction "USBDP_15") (pintype "bidirectional"))
    )
    (net (code "83") (name "/VIN") (class "Default")
      (node (ref "JP15") (pin "6") (pinfunction "6_6") (pintype "passive"))
    )
    (net (code "84") (name "5V") (class "Default")
      (node (ref "B2") (pin "1") (pinfunction "1_1") (pintype "passive"))
      (node (ref "C1") (pin "1") (pinfunction "1_1") (pintype "passive"))
      (node (ref "C10") (pin "1") (pinfunction "1_1") (pintype "passive"))
      (node (ref "C3") (pin "2") (pinfunction "2_2") (pintype "passive"))
      (node (ref "C4") (pin "1") (pinfunction "1_1") (pintype "passive"))
      (node (ref "C5") (pin "1") (pinfunction "1_1") (pintype "passive"))
      (node (ref "C6") (pin "1") (pinfunction "1_1") (pintype "passive"))
      (node (ref "C9") (pin "1") (pinfunction "1_1") (pintype "passive"))
      (node (ref "J3") (pin "2") (pinfunction "2_2") (pintype "passive"))
      (node (ref "JP15") (pin "3") (pinfunction "3_3") (pintype "passive"))
      (node (ref "JP19") (pin "3") (pinfunction "3_3") (pintype "passive"))
      (node (ref "JP20") (pin "3") (pinfunction "3_3") (pintype "passive"))
      (node (ref "JP21") (pin "3") (pinfunction "3_3") (pintype "passive"))
      (node (ref "JP22") (pin "9") (pinfunction "9_9") (pintype "passive"))
      (node (ref "JP23") (pin "3") (pinfunction "3_3") (pintype "passive"))
      (node (ref "JP4") (pin "1") (pinfunction "1_1") (pintype "passive"))
      (node (ref "JP4") (pin "2") (pinfunction "2_2") (pintype "passive"))
      (node (ref "JP7") (pin "4") (pinfunction "4_4") (pintype "passive"))
      (node (ref "JP8") (pin "4") (pinfunction "4_4") (pintype "passive"))
      (node (ref "JP9") (pin "4") (pinfunction "4_4") (pintype "passive"))
      (node (ref "LED6") (pin "A") (pinfunction "A_A") (pintype "passive"))
      (node (ref "LED7") (pin "A") (pinfunction "A_A") (pintype "passive"))
      (node (ref "R1") (pin "1") (pinfunction "1_1") (pintype "passive"))
      (node (ref "R11") (pin "2") (pinfunction "2_2") (pintype "passive"))
      (node (ref "R15") (pin "2") (pinfunction "2_2") (pintype "passive"))
      (node (ref "R19") (pin "2") (pinfunction "2_2") (pintype "passive"))
      (node (ref "R3") (pin "1") (pinfunction "1_1") (pintype "passive"))
      (node (ref "R4") (pin "1") (pinfunction "1_1") (pintype "passive"))
      (node (ref "R5") (pin "2") (pinfunction "2_2") (pintype "passive"))
      (node (ref "R8") (pin "2") (pinfunction "2_2") (pintype "passive"))
      (node (ref "R9") (pin "2") (pinfunction "2_2") (pintype "passive"))
      (node (ref "U$1") (pin "20") (pinfunction "VCC_20") (pintype "bidirectional"))
      (node (ref "U$1") (pin "4") (pinfunction "VCCIO_4") (pintype "bidirectional"))
      (node (ref "U$2") (pin "8") (pinfunction "VDD_8") (pintype "bidirectional"))
      (node (ref "U$3") (pin "2") (pinfunction "VS_2") (pintype "bidirectional"))
      (node (ref "U2") (pin "8") (pinfunction "VDD_8") (pintype "power_in"))
    )
    (net (code "85") (name "GND") (class "Default")
      (node (ref "B1") (pin "2") (pinfunction "2_2") (pintype "passive"))
      (node (ref "C1") (pin "2") (pinfunction "2_2") (pintype "passive"))
      (node (ref "C10") (pin "2") (pinfunction "2_2") (pintype "passive"))
      (node (ref "C2") (pin "2") (pinfunction "2_2") (pintype "passive"))
      (node (ref "C3") (pin "1") (pinfunction "1_1") (pintype "passive"))
      (node (ref "C4") (pin "2") (pinfunction "2_2") (pintype "passive"))
      (node (ref "C5") (pin "2") (pinfunction "2_2") (pintype "passive"))
      (node (ref "C6") (pin "2") (pinfunction "2_2") (pintype "passive"))
      (node (ref "C7") (pin "1") (pinfunction "1_1") (pintype "passive"))
      (node (ref "C8") (pin "2") (pinfunction "2_2") (pintype "passive"))
      (node (ref "C9") (pin "2") (pinfunction "2_2") (pintype "passive"))
      (node (ref "D1") (pin "9") (pinfunction "GND_9") (pintype "bidirectional"))
      (node (ref "D2") (pin "9") (pinfunction "GND_9") (pintype "bidirectional"))
      (node (ref "J1") (pin "1") (pinfunction "1_1") (pintype "passive"))
      (node (ref "J2") (pin "1") (pinfunction "1_1") (pintype "passive"))
      (node (ref "J3") (pin "1") (pinfunction "1_1") (pintype "passive"))
      (node (ref "JP1") (pin "7") (pinfunction "7_7") (pintype "passive"))
      (node (ref "JP10") (pin "3") (pinfunction "3_3") (pintype "passive"))
      (node (ref "JP11") (pin "3") (pinfunction "3_3") (pintype "passive"))
      (node (ref "JP14") (pin "1") (pinfunction "1_1") (pintype "passive"))
      (node (ref "JP14") (pin "2") (pinfunction "2_2") (pintype "passive"))
      (node (ref "JP15") (pin "4") (pinfunction "4_4") (pintype "passive"))
      (node (ref "JP15") (pin "5") (pinfunction "5_5") (pintype "passive"))
      (node (ref "JP20") (pin "4") (pinfunction "4_4") (pintype "passive"))
      (node (ref "JP21") (pin "4") (pinfunction "4_4") (pintype "passive"))
      (node (ref "JP23") (pin "1") (pinfunction "1_1") (pintype "passive"))
      (node (ref "JP25") (pin "1") (pinfunction "1_1") (pintype "passive"))
      (node (ref "JP27") (pin "GND") (pinfunction "GND_GND") (pintype "bidirectional"))
      (node (ref "JP29") (pin "2") (pinfunction "2_2") (pintype "passive"))
      (node (ref "JP30") (pin "2") (pinfunction "2_2") (pintype "passive"))
      (node (ref "JP31") (pin "3") (pinfunction "3_3") (pintype "passive"))
      (node (ref "JP7") (pin "3") (pinfunction "3_3") (pintype "passive"))
      (node (ref "JP8") (pin "3") (pinfunction "3_3") (pintype "passive"))
      (node (ref "JP9") (pin "3") (pinfunction "3_3") (pintype "passive"))
      (node (ref "LED3") (pin "C") (pinfunction "C_C") (pintype "passive"))
      (node (ref "LED4") (pin "C") (pinfunction "C_C") (pintype "passive"))
      (node (ref "M1") (pin "1") (pinfunction "S1_1") (pintype "bidirectional"))
      (node (ref "M1") (pin "3") (pinfunction "S2_3") (pintype "bidirectional"))
      (node (ref "M2") (pin "1") (pinfunction "S1_1") (pintype "bidirectional"))
      (node (ref "R12") (pin "1") (pinfunction "1_1") (pintype "passive"))
      (node (ref "R13") (pin "1") (pinfunction "1_1") (pintype "passive"))
      (node (ref "R14") (pin "1") (pinfunction "1_1") (pintype "passive"))
      (node (ref "R16") (pin "1") (pinfunction "1_1") (pintype "passive"))
      (node (ref "R2") (pin "1") (pinfunction "1_1") (pintype "passive"))
      (node (ref "R6") (pin "2") (pinfunction "2_2") (pintype "passive"))
      (node (ref "S1") (pin "1") (pinfunction "1_1") (pintype "passive"))
      (node (ref "S1") (pin "2") (pinfunction "2_2") (pintype "passive"))
      (node (ref "U$1") (pin "18") (pinfunction "GND2_18") (pintype "bidirectional"))
      (node (ref "U$1") (pin "21") (pinfunction "GND3_21") (pintype "bidirectional"))
      (node (ref "U$1") (pin "25") (pinfunction "AGND_25") (pintype "bidirectional"))
      (node (ref "U$1") (pin "26") (pinfunction "TEST_26") (pintype "bidirectional"))
      (node (ref "U$1") (pin "7") (pinfunction "GND_7") (pintype "bidirectional"))
      (node (ref "U$2") (pin "2") (pinfunction "VSS_2") (pintype "bidirectional"))
      (node (ref "U$3") (pin "3") (pinfunction "GND_3") (pintype "bidirectional"))
      (node (ref "U1") (pin "1") (pinfunction "ADDR_1") (pintype "input"))
      (node (ref "U2") (pin "3") (pinfunction "GND_3") (pintype "passive"))
    )
    (net (code "86") (name "Net-(D1-3C)") (class "Default")
      (node (ref "D1") (pin "16") (pinfunction "3C_16") (pintype "bidirectional"))
      (node (ref "JP6") (pin "3") (pinfunction "3_3") (pintype "passive"))
    )
    (net (code "87") (name "Net-(D1-4C)") (class "Default")
      (node (ref "D1") (pin "15") (pinfunction "4C_15") (pintype "bidirectional"))
      (node (ref "JP6") (pin "4") (pinfunction "4_4") (pintype "passive"))
    )
    (net (code "88") (name "Net-(D1-5C)") (class "Default")
      (node (ref "D1") (pin "14") (pinfunction "5C_14") (pintype "bidirectional"))
      (node (ref "JP6") (pin "5") (pinfunction "5_5") (pintype "passive"))
    )
    (net (code "89") (name "Net-(D1-6C)") (class "Default")
      (node (ref "D1") (pin "13") (pinfunction "6C_13") (pintype "bidirectional"))
      (node (ref "JP6") (pin "6") (pinfunction "6_6") (pintype "passive"))
    )
    (net (code "90") (name "Net-(D1-7C)") (class "Default")
      (node (ref "D1") (pin "12") (pinfunction "7C_12") (pintype "bidirectional"))
      (node (ref "JP6") (pin "7") (pinfunction "7_7") (pintype "passive"))
    )
    (net (code "91") (name "Net-(D1-8C)") (class "Default")
      (node (ref "D1") (pin "11") (pinfunction "8C_11") (pintype "bidirectional"))
      (node (ref "JP6") (pin "8") (pinfunction "8_8") (pintype "passive"))
    )
    (net (code "92") (name "Net-(D2-1C)") (class "Default")
      (node (ref "D2") (pin "18") (pinfunction "1C_18") (pintype "bidirectional"))
      (node (ref "JP5") (pin "1") (pinfunction "1_1") (pintype "passive"))
    )
    (net (code "93") (name "Net-(D2-2C)") (class "Default")
      (node (ref "D2") (pin "17") (pinfunction "2C_17") (pintype "bidirectional"))
      (node (ref "JP5") (pin "2") (pinfunction "2_2") (pintype "passive"))
    )
    (net (code "94") (name "Net-(D2-3C)") (class "Default")
      (node (ref "D2") (pin "16") (pinfunction "3C_16") (pintype "bidirectional"))
      (node (ref "JP5") (pin "3") (pinfunction "3_3") (pintype "passive"))
    )
    (net (code "95") (name "Net-(D2-4C)") (class "Default")
      (node (ref "D2") (pin "15") (pinfunction "4C_15") (pintype "bidirectional"))
      (node (ref "JP5") (pin "4") (pinfunction "4_4") (pintype "passive"))
    )
    (net (code "96") (name "Net-(D2-5C)") (class "Default")
      (node (ref "D2") (pin "14") (pinfunction "5C_14") (pintype "bidirectional"))
      (node (ref "JP5") (pin "5") (pinfunction "5_5") (pintype "passive"))
    )
    (net (code "97") (name "Net-(D2-6C)") (class "Default")
      (node (ref "D2") (pin "13") (pinfunction "6C_13") (pintype "bidirectional"))
      (node (ref "JP5") (pin "6") (pinfunction "6_6") (pintype "passive"))
    )
    (net (code "98") (name "Net-(D2-7C)") (class "Default")
      (node (ref "D2") (pin "12") (pinfunction "7C_12") (pintype "bidirectional"))
      (node (ref "JP5") (pin "7") (pinfunction "7_7") (pintype "passive"))
    )
    (net (code "99") (name "Net-(D2-8C)") (class "Default")
      (node (ref "D2") (pin "11") (pinfunction "8C_11") (pintype "bidirectional"))
      (node (ref "JP5") (pin "8") (pinfunction "8_8") (pintype "passive"))
    )
    (net (code "100") (name "Net-(JP27-PadVBUS)") (class "Default")
      (node (ref "JP27") (pin "VBUS") (pinfunction "VBUS_VBUS") (pintype "bidirectional"))
      (node (ref "R10") (pin "1") (pinfunction "1_1") (pintype "passive"))
    )
    (net (code "101") (name "Net-(LED1-PadC)") (class "Default")
      (node (ref "LED1") (pin "C") (pinfunction "C_C") (pintype "passive"))
      (node (ref "R14") (pin "2") (pinfunction "2_2") (pintype "passive"))
    )
    (net (code "102") (name "Net-(LED2-PadC)") (class "Default")
      (node (ref "LED2") (pin "C") (pinfunction "C_C") (pintype "passive"))
      (node (ref "R13") (pin "2") (pinfunction "2_2") (pintype "passive"))
    )
    (net (code "103") (name "Net-(LED3-PadA)") (class "Default")
      (node (ref "LED3") (pin "A") (pinfunction "A_A") (pintype "passive"))
      (node (ref "R8") (pin "1") (pinfunction "1_1") (pintype "passive"))
    )
    (net (code "104") (name "Net-(LED4-PadA)") (class "Default")
      (node (ref "LED4") (pin "A") (pinfunction "A_A") (pintype "passive"))
      (node (ref "R7") (pin "1") (pinfunction "1_1") (pintype "passive"))
    )
    (net (code "105") (name "Net-(LED5-PadC)") (class "Default")
      (node (ref "LED5") (pin "C") (pinfunction "C_C") (pintype "passive"))
      (node (ref "R12") (pin "2") (pinfunction "2_2") (pintype "passive"))
    )
    (net (code "106") (name "Net-(LED6-PadC)") (class "Default")
      (node (ref "LED6") (pin "C") (pinfunction "C_C") (pintype "passive"))
      (node (ref "R18") (pin "2") (pinfunction "2_2") (pintype "passive"))
    )
    (net (code "107") (name "Net-(LED7-PadC)") (class "Default")
      (node (ref "LED7") (pin "C") (pinfunction "C_C") (pintype "passive"))
      (node (ref "R17") (pin "2") (pinfunction "2_2") (pintype "passive"))
    )
    (net (code "108") (name "Net-(M1-D1_B)") (class "Default")
      (node (ref "JP26") (pin "2") (pinfunction "2_2") (pintype "passive"))
      (node (ref "M1") (pin "7") (pinfunction "D1_B_7") (pintype "bidirectional"))
    )
    (net (code "109") (name "Net-(M1-D2_A)") (class "Default")
      (node (ref "JP26") (pin "3") (pinfunction "3_3") (pintype "passive"))
      (node (ref "M1") (pin "6") (pinfunction "D2_A_6") (pintype "bidirectional"))
    )
    (net (code "110") (name "Net-(M2-D1_A)") (class "Default")
      (node (ref "JP26") (pin "4") (pinfunction "4_4") (pintype "passive"))
      (node (ref "M2") (pin "8") (pinfunction "D1_A_8") (pintype "bidirectional"))
    )
    (net (code "111") (name "Net-(U$1-3V3OUT)") (class "Default")
      (node (ref "C7") (pin "2") (pinfunction "2_2") (pintype "passive"))
      (node (ref "U$1") (pin "17") (pinfunction "3V3OUT_17") (pintype "bidirectional"))
    )
    (net (code "112") (name "Net-(U$1-RESET#)") (class "Default")
      (node (ref "R10") (pin "2") (pinfunction "2_2") (pintype "passive"))
      (node (ref "R6") (pin "1") (pinfunction "1_1") (pintype "passive"))
      (node (ref "U$1") (pin "19") (pinfunction "RESET#_19") (pintype "bidirectional"))
    )
    (net (code "113") (name "Net-(U$2-VCORE)") (class "Default")
      (node (ref "C2") (pin "1") (pinfunction "1_1") (pintype "passive"))
      (node (ref "U$2") (pin "1") (pinfunction "VCORE_1") (pintype "bidirectional"))
    )
    (net (code "114") (name "Net-(U1-AIN0)") (class "Default")
      (node (ref "JP28") (pin "1") (pinfunction "1_1") (pintype "passive"))
      (node (ref "U1") (pin "4") (pinfunction "AIN0_4") (pintype "input"))
    )
    (net (code "115") (name "Net-(U1-ALERT{slash}RDY)") (class "Default")
      (node (ref "R11") (pin "1") (pinfunction "1_1") (pintype "passive"))
      (node (ref "U1") (pin "2") (pinfunction "ALERT/RDY_2") (pintype "input"))
    )
    (net (code "116") (name "Net-(U1-GND)") (class "Default")
      (node (ref "B1") (pin "1") (pinfunction "1_1") (pintype "passive"))
      (node (ref "U1") (pin "3") (pinfunction "GND_3") (pintype "passive"))
    )
    (net (code "117") (name "Net-(U1-VDD)") (class "Default")
      (node (ref "B2") (pin "2") (pinfunction "2_2") (pintype "passive"))
      (node (ref "U1") (pin "8") (pinfunction "VDD_8") (pintype "power_in"))
    )
    (net (code "118") (name "Net-(U2-ADDR)") (class "Default")
      (node (ref "R19") (pin "1") (pinfunction "1_1") (pintype "passive"))
      (node (ref "U2") (pin "1") (pinfunction "ADDR_1") (pintype "input"))
    )
    (net (code "119") (name "Net-(U2-ALERT{slash}RDY)") (class "Default")
      (node (ref "R15") (pin "1") (pinfunction "1_1") (pintype "passive"))
      (node (ref "U2") (pin "2") (pinfunction "ALERT/RDY_2") (pintype "input"))
    )
    (net (code "120") (name "unconnected-(D1-1B-Pad1)") (class "Default")
      (node (ref "D1") (pin "1") (pinfunction "1B_1") (pintype "bidirectional"))
    )
    (net (code "121") (name "unconnected-(D1-1C-Pad18)") (class "Default")
      (node (ref "D1") (pin "18") (pinfunction "1C_18") (pintype "bidirectional"))
    )
    (net (code "122") (name "unconnected-(D1-2B-Pad2)") (class "Default")
      (node (ref "D1") (pin "2") (pinfunction "2B_2") (pintype "bidirectional"))
    )
    (net (code "123") (name "unconnected-(D1-2C-Pad17)") (class "Default")
      (node (ref "D1") (pin "17") (pinfunction "2C_17") (pintype "bidirectional"))
    )
    (net (code "124") (name "unconnected-(JP6-Pad2)") (class "Default")
      (node (ref "JP6") (pin "2") (pinfunction "2_2") (pintype "passive"))
    )
    (net (code "125") (name "unconnected-(JP10-Pad2)") (class "Default")
      (node (ref "JP10") (pin "2") (pinfunction "2_2") (pintype "passive"))
    )
    (net (code "126") (name "unconnected-(JP11-Pad2)") (class "Default")
      (node (ref "JP11") (pin "2") (pinfunction "2_2") (pintype "passive"))
    )
    (net (code "127") (name "unconnected-(M1-D1_A-Pad8)") (class "Default")
      (node (ref "M1") (pin "8") (pinfunction "D1_A_8") (pintype "bidirectional"))
    )
    (net (code "128") (name "unconnected-(M1-D2_B-Pad5)") (class "Default")
      (node (ref "M1") (pin "5") (pinfunction "D2_B_5") (pintype "bidirectional"))
    )
    (net (code "129") (name "unconnected-(M2-D1_B-Pad7)") (class "Default")
      (node (ref "M2") (pin "7") (pinfunction "D1_B_7") (pintype "bidirectional"))
    )
    (net (code "130") (name "unconnected-(M2-D2_A-Pad6)") (class "Default")
      (node (ref "M2") (pin "6") (pinfunction "D2_A_6") (pintype "bidirectional"))
    )
    (net (code "131") (name "unconnected-(M2-D2_B-Pad5)") (class "Default")
      (node (ref "M2") (pin "5") (pinfunction "D2_B_5") (pintype "bidirectional"))
    )
    (net (code "132") (name "unconnected-(M2-G2-Pad4)") (class "Default")
      (node (ref "M2") (pin "4") (pinfunction "G2_4") (pintype "bidirectional"))
    )
    (net (code "133") (name "unconnected-(M2-S2-Pad3)") (class "Default")
      (node (ref "M2") (pin "3") (pinfunction "S2_3") (pintype "bidirectional"))
    )
    (net (code "134") (name "unconnected-(U$1-CBUS2-Pad13)") (class "Default")
      (node (ref "U$1") (pin "13") (pinfunction "CBUS2_13") (pintype "bidirectional"))
    )
    (net (code "135") (name "unconnected-(U$1-CBUS3-Pad14)") (class "Default")
      (node (ref "U$1") (pin "14") (pinfunction "CBUS3_14") (pintype "bidirectional"))
    )
    (net (code "136") (name "unconnected-(U$1-CBUS4-Pad12)") (class "Default")
      (node (ref "U$1") (pin "12") (pinfunction "CBUS4_12") (pintype "bidirectional"))
    )
    (net (code "137") (name "unconnected-(U$1-CTS-Pad11)") (class "Default")
      (node (ref "U$1") (pin "11") (pinfunction "CTS_11") (pintype "bidirectional"))
    )
    (net (code "138") (name "unconnected-(U$1-DCD-Pad10)") (class "Default")
      (node (ref "U$1") (pin "10") (pinfunction "DCD_10") (pintype "bidirectional"))
    )
    (net (code "139") (name "unconnected-(U$1-DSR-Pad9)") (class "Default")
      (node (ref "U$1") (pin "9") (pinfunction "DSR_9") (pintype "bidirectional"))
    )
    (net (code "140") (name "unconnected-(U$1-DTR-Pad2)") (class "Default")
      (node (ref "U$1") (pin "2") (pinfunction "DTR_2") (pintype "bidirectional"))
    )
    (net (code "141") (name "unconnected-(U$1-NC-Pad8)") (class "Default")
      (node (ref "U$1") (pin "8") (pinfunction "NC_8") (pintype "bidirectional"))
    )
    (net (code "142") (name "unconnected-(U$1-NC2-Pad24)") (class "Default")
      (node (ref "U$1") (pin "24") (pinfunction "NC2_24") (pintype "bidirectional"))
    )
    (net (code "143") (name "unconnected-(U$1-OSCI-Pad27)") (class "Default")
      (node (ref "U$1") (pin "27") (pinfunction "OSCI_27") (pintype "bidirectional"))
    )
    (net (code "144") (name "unconnected-(U$1-OSCO-Pad28)") (class "Default")
      (node (ref "U$1") (pin "28") (pinfunction "OSCO_28") (pintype "bidirectional"))
    )
    (net (code "145") (name "unconnected-(U$1-RI-Pad6)") (class "Default")
      (node (ref "U$1") (pin "6") (pinfunction "RI_6") (pintype "bidirectional"))
    )
    (net (code "146") (name "unconnected-(U$1-RTS-Pad3)") (class "Default")
      (node (ref "U$1") (pin "3") (pinfunction "RTS_3") (pintype "bidirectional"))
    )
    (net (code "147") (name "unconnected-(U$2-AL_H-Pad5)") (class "Default")
      (node (ref "U$2") (pin "5") (pinfunction "AL_H_5") (pintype "bidirectional"))
    )
    (net (code "148") (name "unconnected-(U$2-AL_L-Pad6)") (class "Default")
      (node (ref "U$2") (pin "6") (pinfunction "AL_L_6") (pintype "bidirectional"))
    )
    (net (code "149") (name "unconnected-(U$2-NC-Pad7)") (class "Default")
      (node (ref "U$2") (pin "7") (pinfunction "NC_7") (pintype "bidirectional"))
    )
    (net (code "150") (name "unconnected-(U1-AIN1-Pad5)") (class "Default")
      (node (ref "U1") (pin "5") (pinfunction "AIN1_5") (pintype "input"))
    )
    (net (code "151") (name "unconnected-(U1-AIN2-Pad6)") (class "Default")
      (node (ref "U1") (pin "6") (pinfunction "AIN2_6") (pintype "input"))
    )
    (net (code "152") (name "unconnected-(U1-AIN3-Pad7)") (class "Default")
      (node (ref "U1") (pin "7") (pinfunction "AIN3_7") (pintype "input"))
    )
    (net (code "153") (name "unconnected-(U2-AIN2-Pad6)") (class "Default")
      (node (ref "U2") (pin "6") (pinfunction "AIN2_6") (pintype "input"))
    )
    (net (code "154") (name "unconnected-(U2-AIN3-Pad7)") (class "Default")
      (node (ref "U2") (pin "7") (pinfunction "AIN3_7") (pintype "input"))
    )
  )
)
